# Top.net
KiCad netlist of a schematic drawn in Altium Designer
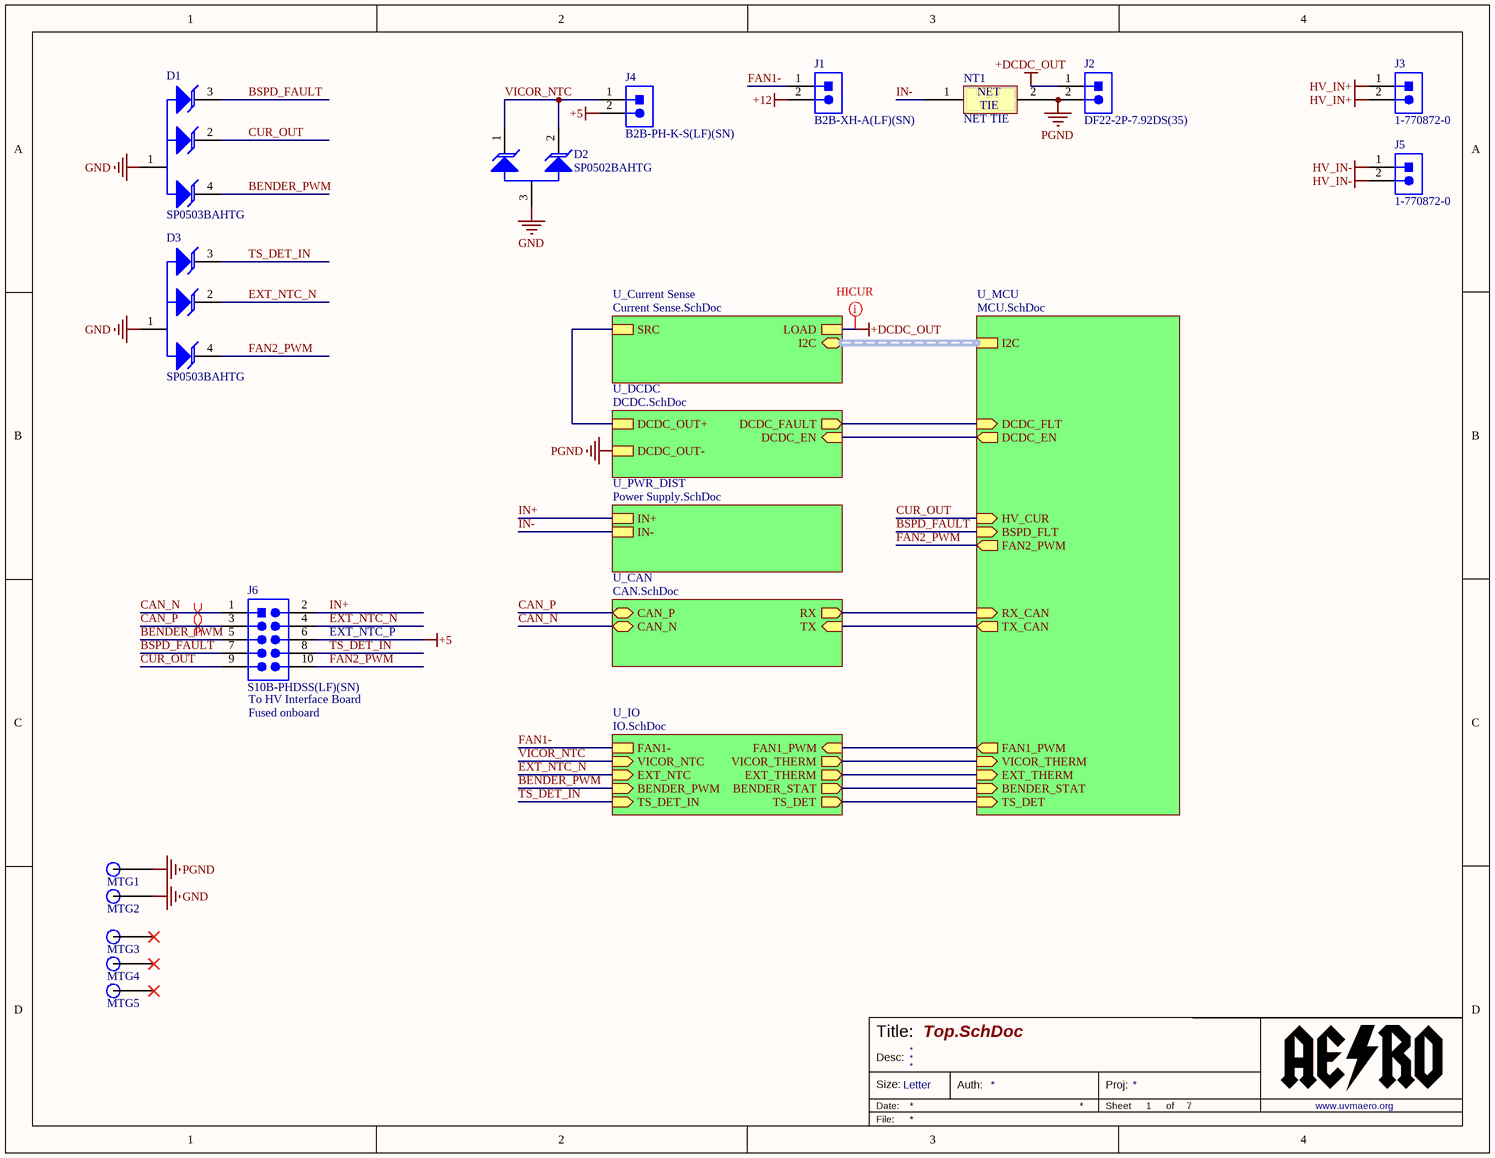
[diagram p0: Top.SchDoc]

(export (version "E")
  (design (tool "Eeschema 10.0.6"))
  (components
    (comp (ref "D1")
      (value "SP0503BAHTG")
      (footprint "Littelfuse_SP0503BAHTG_0")
      (description "8.5V Clamp  Ipp Tvs Diode Surface Mount SOT-23-5 5.5V")
      (fields (field (name "MANUFACTURER") "Littelfuse"))
      (libsource (lib "AERO Parts") (part "SP0503BAHTG"))
    )
    (comp (ref "D2")
      (value "SP0502BAHTG")
      (footprint "TO-236 SOT23")
      (description "8.5V Clamp  Ipp Tvs Diode Surface Mount SOT-23-5 5.5V")
      (fields (field (name "MANUFACTURER") "Littelfuse"))
      (libsource (lib "AERO Parts") (part "SP0502BAHTG"))
    )
    (comp (ref "D3")
      (value "SP0503BAHTG")
      (footprint "Littelfuse_SP0503BAHTG_0")
      (description "8.5V Clamp  Ipp Tvs Diode Surface Mount SOT-23-5 5.5V")
      (fields (field (name "MANUFACTURER") "Littelfuse"))
      (libsource (lib "AERO Parts") (part "SP0503BAHTG"))
    )
    (comp (ref "J1")
      (value "B2B-XH-A(LF)(SN)")
      (footprint "B2B-XH-A(LF)(SN)")
      (description "CONN HEADER VERT 2POS 2.5MM")
      (fields (field (name "MANUFACTURER") "JST"))
      (libsource (lib "AERO Parts") (part "B2B-XH-A(LF)(SN)"))
    )
    (comp (ref "J2")
      (value "DF22-2P-7.92DS(35)")
      (footprint "CON2-1X2_RZ_DF22")
      (description "Connector Header Through Hole, Right Angle 2 position 0.312\" (7.92mm)")
      (fields (field (name "MANUFACTURER") "Hirose"))
      (libsource (lib "AERO Parts") (part "DF22-2P-7.92DS(35)"))
    )
    (comp (ref "J3")
      (value "1-770872-0")
      (footprint "CON2_1X2_P163_VM")
      (description "Connector Header Through Hole 2 position 0.163\" (4.14mm)")
      (fields
        (field (name "MANUFACTURER") "TE Connectivity")
        (field (name "COPYRIGHT") "Copyright (C) 2018 Accelerated Designs. All rights reserved")
      )
      (libsource (lib "AERO Parts") (part "1-770872-0"))
    )
    (comp (ref "J4")
      (value "B2B-PH-K-S(LF)(SN)")
      (footprint "JST_Sales_America_Inc._B2B-PH-K-S_LF_SN_0")
      (description "Connector Header Through Hole 2 position 0.079\" (2.00mm)")
      (fields (field (name "MANUFACTURER") "JST") (field (name "MANUFACTURER PART NUMBER") "B2BPHKSLFSN"))
      (libsource (lib "AERO Parts") (part "B2B-PH-K-S(LF)(SN)"))
    )
    (comp (ref "J5")
      (value "1-770872-0")
      (footprint "CON2_1X2_P163_VM")
      (description "Connector Header Through Hole 2 position 0.163\" (4.14mm)")
      (fields
        (field (name "MANUFACTURER") "TE Connectivity")
        (field (name "COPYRIGHT") "Copyright (C) 2018 Accelerated Designs. All rights reserved")
      )
      (libsource (lib "AERO Parts") (part "1-770872-0"))
    )
    (comp (ref "J6")
      (value "S10B-PHDSS(LF)(SN)")
      (footprint "S10B-PHDSS")
      (description "Connector Header Through Hole, Right Angle 10 position 0.079\" (2.00mm)")
      (fields (field (name "MANUFACTURER") "JST"))
      (libsource (lib "AERO Parts") (part "S10B-PHDSS(LF)(SN)"))
    )
    (comp (ref "MTG1")
      (value "PCB MTG M3")
      (footprint "MTG-M3")
      (description "PCB Mounting for M3 Screw")
      (libsource (lib "Hardware") (part "MTG"))
    )
    (comp (ref "MTG2")
      (value "PCB MTG M3")
      (footprint "MTG-M3")
      (description "PCB Mounting for M3 Screw")
      (libsource (lib "Hardware") (part "MTG"))
    )
    (comp (ref "MTG3")
      (value "PCB MTG M3 HV")
      (footprint "MTG-M3-HV")
      (description "PCB Mounting for M3 Screw - HV")
      (libsource (lib "Hardware") (part "MTG"))
    )
    (comp (ref "MTG4")
      (value "PCB MTG M3 HV")
      (footprint "MTG-M3-HV")
      (description "PCB Mounting for M3 Screw - HV")
      (libsource (lib "Hardware") (part "MTG"))
    )
    (comp (ref "MTG5")
      (value "PCB MTG M3 HV")
      (footprint "MTG-M3-HV")
      (description "PCB Mounting for M3 Screw - HV")
      (libsource (lib "Hardware") (part "MTG"))
    )
    (comp (ref "NT1")
      (value "NET TIE")
      (footprint "60MIL_TIE")
      (description "Net Tie (No BOM)")
      (libsource (lib "AERO Parts") (part "NET TIE"))
    )
  )
  (nets
    (net (code "1") (name "+5") (class "Default")
      (node (ref "J4") (pin "2") (pinfunction "2_2") (pintype "passive"))
      (node (ref "J6") (pin "6") (pinfunction "6_6") (pintype "passive"))
    )
    (net (code "2") (name "+12") (class "Default")
      (node (ref "J1") (pin "2") (pinfunction "2_2") (pintype "passive"))
    )
    (net (code "3") (name "+DCDC_OUT") (class "Default")
      (node (ref "J2") (pin "1") (pinfunction "1_1") (pintype "passive"))
    )
    (net (code "4") (name "/BENDER_PWM") (class "Default")
      (node (ref "D1") (pin "4") (pinfunction "4_4") (pintype "passive"))
      (node (ref "J6") (pin "5") (pinfunction "5_5") (pintype "passive"))
    )
    (net (code "6") (name "/BSPD_FAULT") (class "Default")
      (node (ref "D1") (pin "3") (pinfunction "3_3") (pintype "passive"))
      (node (ref "J6") (pin "7") (pinfunction "7_7") (pintype "passive"))
    )
    (net (code "7") (name "/CAN_N") (class "Default")
      (node (ref "J6") (pin "1") (pinfunction "1_1") (pintype "passive"))
    )
    (net (code "8") (name "/CAN_P") (class "Default")
      (node (ref "J6") (pin "3") (pinfunction "3_3") (pintype "passive"))
    )
    (net (code "9") (name "/CUR_OUT") (class "Default")
      (node (ref "D1") (pin "2") (pinfunction "2_2") (pintype "passive"))
      (node (ref "J6") (pin "9") (pinfunction "9_9") (pintype "passive"))
    )
    (net (code "13") (name "/EXT_NTC_N") (class "Default")
      (node (ref "D3") (pin "2") (pinfunction "2_2") (pintype "passive"))
      (node (ref "J6") (pin "4") (pinfunction "4_4") (pintype "passive"))
    )
    (net (code "15") (name "/FAN1-") (class "Default")
      (node (ref "J1") (pin "1") (pinfunction "1_1") (pintype "passive"))
    )
    (net (code "17") (name "/FAN2_PWM") (class "Default")
      (node (ref "D3") (pin "4") (pinfunction "4_4") (pintype "passive"))
      (node (ref "J6") (pin "10") (pinfunction "10_10") (pintype "passive"))
    )
    (net (code "19") (name "/IN+") (class "Default")
      (node (ref "J6") (pin "2") (pinfunction "2_2") (pintype "passive"))
    )
    (net (code "20") (name "/IN-") (class "Default") (node (ref "NT1") (pin "1") (pintype "passive")))
    (net (code "23") (name "/TS_DET_IN") (class "Default")
      (node (ref "D3") (pin "3") (pinfunction "3_3") (pintype "passive"))
      (node (ref "J6") (pin "8") (pinfunction "8_8") (pintype "passive"))
    )
    (net (code "25") (name "/VICOR_NTC") (class "Default")
      (node (ref "D2") (pin "1") (pinfunction "1_1") (pintype "passive"))
      (node (ref "D2") (pin "2") (pinfunction "2_2") (pintype "passive"))
      (node (ref "J4") (pin "1") (pinfunction "1_1") (pintype "passive"))
    )
    (net (code "27") (name "GND") (class "Default")
      (node (ref "D1") (pin "1") (pinfunction "1_1") (pintype "passive"))
      (node (ref "D2") (pin "3") (pinfunction "3_3") (pintype "passive"))
      (node (ref "D3") (pin "1") (pinfunction "1_1") (pintype "passive"))
      (node (ref "MTG2") (pin "1") (pinfunction "1_1") (pintype "passive"))
    )
    (net (code "28") (name "HV_IN+") (class "Default")
      (node (ref "J3") (pin "1") (pinfunction "1_1") (pintype "passive"))
      (node (ref "J3") (pin "2") (pinfunction "2_2") (pintype "passive"))
    )
    (net (code "29") (name "HV_IN-") (class "Default")
      (node (ref "J5") (pin "1") (pinfunction "1_1") (pintype "passive"))
      (node (ref "J5") (pin "2") (pinfunction "2_2") (pintype "passive"))
    )
    (net (code "30") (name "PGND") (class "Default")
      (node (ref "J2") (pin "2") (pinfunction "2_2") (pintype "passive"))
      (node (ref "MTG1") (pin "1") (pinfunction "1_1") (pintype "passive"))
      (node (ref "NT1") (pin "2") (pintype "passive"))
    )
    (net (code "31") (name "unconnected-(MTG3-Pad1)") (class "Default")
      (node (ref "MTG3") (pin "1") (pinfunction "1_1") (pintype "passive+no_connect"))
    )
    (net (code "32") (name "unconnected-(MTG4-Pad1)") (class "Default")
      (node (ref "MTG4") (pin "1") (pinfunction "1_1") (pintype "passive+no_connect"))
    )
    (net (code "33") (name "unconnected-(MTG5-Pad1)") (class "Default")
      (node (ref "MTG5") (pin "1") (pinfunction "1_1") (pintype "passive+no_connect"))
    )
  )
)
